# Sudden_XCVF_Driver_Stage.net
KiCad netlist of a schematic drawn in EAGLE
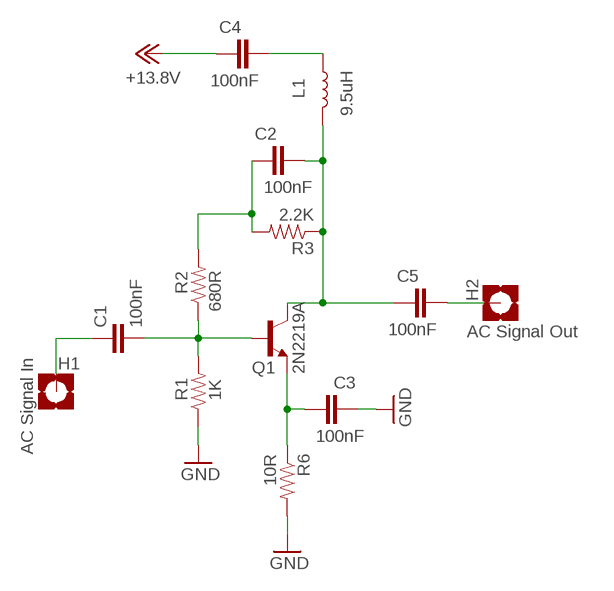
[diagram p0: schematic, sheet 1]

(export (version "E")
  (design (tool "Eeschema 10.0.6"))
  (components
    (comp (ref "C1")
      (value "100nF")
      (footprint "eagle-import:CAP-MEDIUM-MUPPET")
      (libsource (lib "eagle-import") (part "CAP-MEDIUM-MUPPET"))
    )
    (comp (ref "C2")
      (value "100nF")
      (footprint "eagle-import:CAP-MEDIUM-MUPPET")
      (libsource (lib "eagle-import") (part "CAP-MEDIUM-MUPPET"))
    )
    (comp (ref "C3")
      (value "100nF")
      (footprint "eagle-import:CAP-MEDIUM-MUPPET")
      (libsource (lib "eagle-import") (part "CAP-MEDIUM-MUPPET"))
    )
    (comp (ref "C4")
      (value "100nF")
      (footprint "eagle-import:CAP-MEDIUM-MUPPET")
      (libsource (lib "eagle-import") (part "CAP-MEDIUM-MUPPET"))
    )
    (comp (ref "C5")
      (value "100nF")
      (footprint "eagle-import:CAP-MEDIUM-MUPPET")
      (libsource (lib "eagle-import") (part "CAP-MEDIUM-MUPPET"))
    )
    (comp (ref "H1")
      (value "AC Signal In")
      (footprint "eagle-import:PAD-SQUARE")
      (libsource (lib "eagle-import") (part "MOUNT-PAD-SQUARE4.5"))
    )
    (comp (ref "H2")
      (value "AC Signal Out")
      (footprint "eagle-import:PAD-SQUARE")
      (libsource (lib "eagle-import") (part "MOUNT-PAD-SQUARE4.5"))
    )
    (comp (ref "L1")
      (value "9.5uH")
      (footprint "eagle-import:INDUCTOR_2.2UH")
      (libsource (lib "eagle-import") (part "INDUCTOR-VLF4012AT-2.2UH"))
    )
    (comp (ref "P+1")
      (value "+13.8V")
      (footprint "eagle-import:POWER-IN-PAD")
      (libsource (lib "eagle-import") (part "+12V"))
    )
    (comp (ref "Q1")
      (value "2N2219A")
      (footprint "eagle-import:2N2222-TO18")
      (libsource (lib "eagle-import") (part "2N2222"))
    )
    (comp (ref "R1")
      (value "1K")
      (footprint "eagle-import:RESITOR-MUPPET")
      (libsource (lib "eagle-import") (part "RESISTOR-MUPPETMEDIUM-RESISTOR-PADS"))
    )
    (comp (ref "R2")
      (value "680R")
      (footprint "eagle-import:RESITOR-MUPPET")
      (libsource (lib "eagle-import") (part "RESISTOR-MUPPETMEDIUM-RESISTOR-PADS"))
    )
    (comp (ref "R3")
      (value "2.2K")
      (footprint "eagle-import:RESITOR-MUPPET")
      (libsource (lib "eagle-import") (part "RESISTOR-MUPPETMEDIUM-RESISTOR-PADS"))
    )
    (comp (ref "R6")
      (value "10R")
      (footprint "eagle-import:RESITOR-MUPPET")
      (libsource (lib "eagle-import") (part "RESISTOR-MUPPETMEDIUM-RESISTOR-PADS"))
    )
  )
  (nets
    (net (code "1") (name "+13.8V") (class "Default")
      (node (ref "C4") (pin "1") (pinfunction "1_1") (pintype "passive"))
      (node (ref "P+1") (pin "VCC") (pinfunction "+12V_VCC") (pintype "power_in"))
    )
    (net (code "2") (name "GND") (class "Default")
      (node (ref "C3") (pin "1") (pinfunction "1_1") (pintype "passive"))
      (node (ref "R1") (pin "P$1") (pinfunction "1_P$1") (pintype "passive"))
      (node (ref "R6") (pin "P$2") (pinfunction "2_P$2") (pintype "passive"))
    )
    (net (code "3") (name "Net-(H1-MOUNT)") (class "Default")
      (node (ref "C1") (pin "1") (pinfunction "1_1") (pintype "passive"))
      (node (ref "H1") (pin "PAD") (pinfunction "MOUNT_PAD") (pintype "passive"))
    )
    (net (code "4") (name "Net-(H2-MOUNT)") (class "Default")
      (node (ref "C5") (pin "2") (pinfunction "2_2") (pintype "passive"))
      (node (ref "H2") (pin "PAD") (pinfunction "MOUNT_PAD") (pintype "passive"))
    )
    (net (code "5") (name "Net-(L1-1)") (class "Default")
      (node (ref "C4") (pin "2") (pinfunction "2_2") (pintype "passive"))
      (node (ref "L1") (pin "P$1") (pinfunction "1_P$1") (pintype "passive"))
    )
    (net (code "6") (name "Net-(L1-2)") (class "Default")
      (node (ref "C2") (pin "2") (pinfunction "2_2") (pintype "passive"))
      (node (ref "C5") (pin "1") (pinfunction "1_1") (pintype "passive"))
      (node (ref "L1") (pin "P$2") (pinfunction "2_P$2") (pintype "passive"))
      (node (ref "Q1") (pin "3") (pinfunction "C_3") (pintype "passive"))
      (node (ref "R3") (pin "P$1") (pinfunction "1_P$1") (pintype "passive"))
    )
    (net (code "7") (name "Net-(Q1-B)") (class "Default")
      (node (ref "C1") (pin "2") (pinfunction "2_2") (pintype "passive"))
      (node (ref "Q1") (pin "2") (pinfunction "B_2") (pintype "passive"))
      (node (ref "R1") (pin "P$2") (pinfunction "2_P$2") (pintype "passive"))
      (node (ref "R2") (pin "P$1") (pinfunction "1_P$1") (pintype "passive"))
    )
    (net (code "8") (name "Net-(Q1-E)") (class "Default")
      (node (ref "C3") (pin "2") (pinfunction "2_2") (pintype "passive"))
      (node (ref "Q1") (pin "1") (pinfunction "E_1") (pintype "passive"))
      (node (ref "R6") (pin "P$1") (pinfunction "1_P$1") (pintype "passive"))
    )
    (net (code "9") (name "Net-(R2-2)") (class "Default")
      (node (ref "C2") (pin "1") (pinfunction "1_1") (pintype "passive"))
      (node (ref "R2") (pin "P$2") (pinfunction "2_P$2") (pintype "passive"))
      (node (ref "R3") (pin "P$2") (pinfunction "2_P$2") (pintype "passive"))
    )
  )
)
